# Scan.net
KiCad netlist of a schematic drawn in Altium Designer
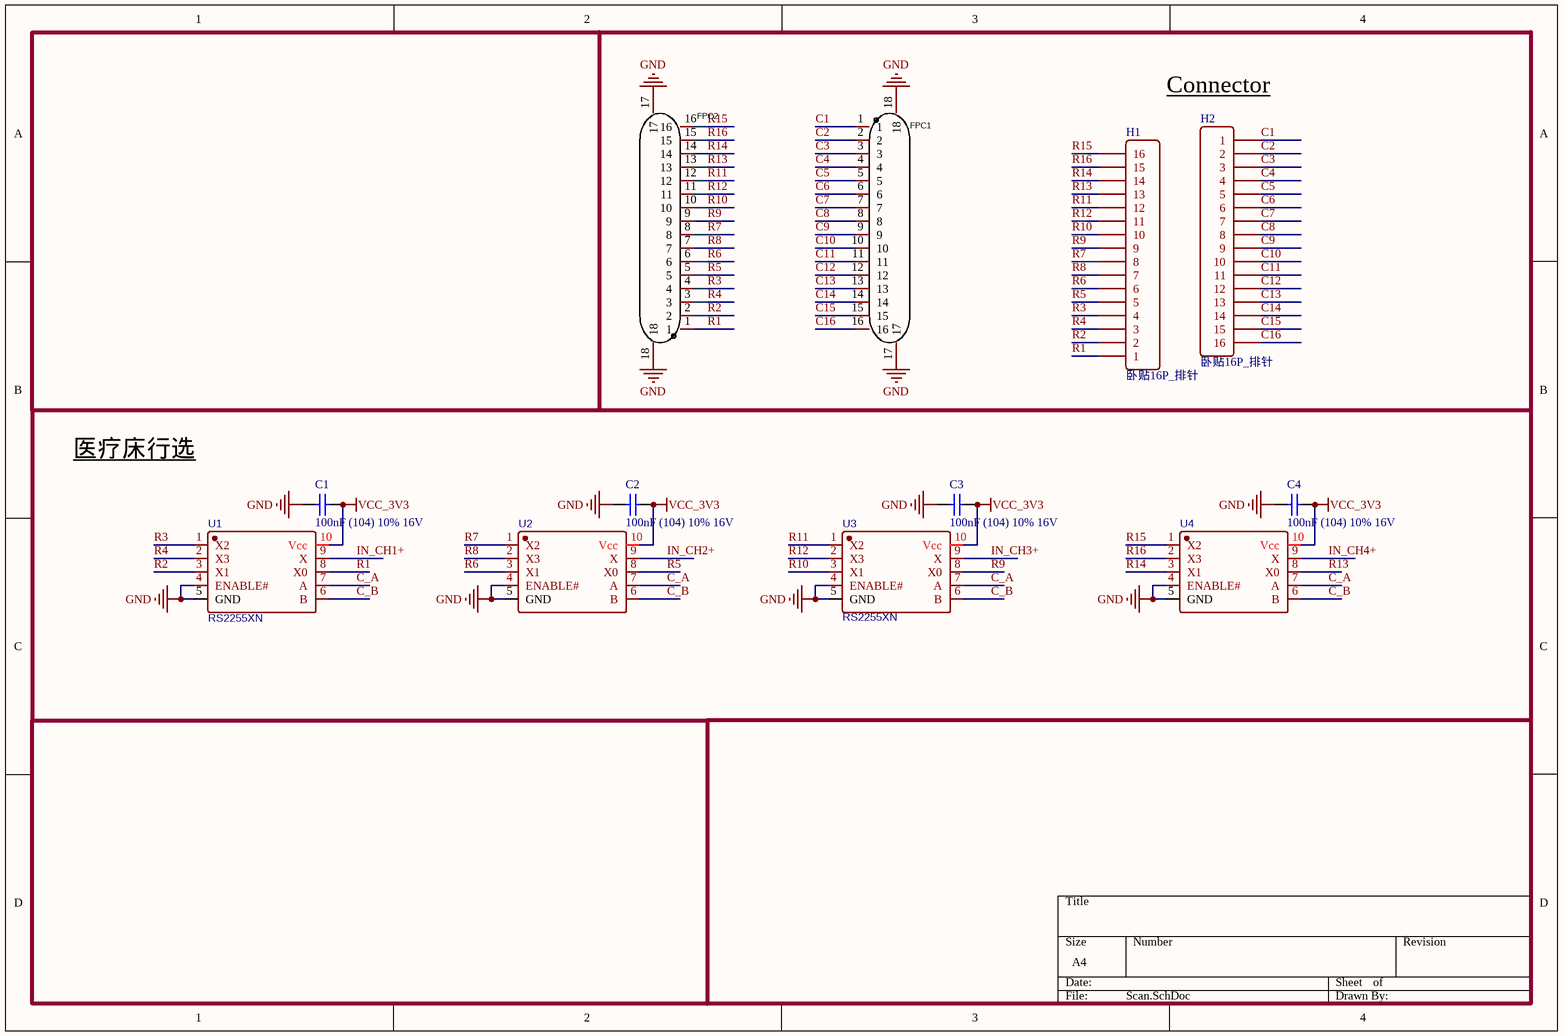
[diagram p0: Scan.SchDoc]

(export (version "E")
  (design (tool "Eeschema 10.0.6"))
  (components
    (comp (ref "C1")
      (value "100nF (104) 10% 16V")
      (footprint "0402_C")
      (description "贴片电容")
      (libsource (lib "Miscellaneous Devices LC") (part "0402 100nF (104) 10% 16V"))
    )
    (comp (ref "C2")
      (value "100nF (104) 10% 16V")
      (footprint "0402_C")
      (description "贴片电容")
      (libsource (lib "Miscellaneous Devices LC") (part "0402 100nF (104) 10% 16V"))
    )
    (comp (ref "C3")
      (value "100nF (104) 10% 16V")
      (footprint "0402_C")
      (description "贴片电容")
      (libsource (lib "Miscellaneous Devices LC") (part "0402 100nF (104) 10% 16V"))
    )
    (comp (ref "C4")
      (value "100nF (104) 10% 16V")
      (footprint "0402_C")
      (description "贴片电容")
      (libsource (lib "Miscellaneous Devices LC") (part "0402 100nF (104) 10% 16V"))
    )
    (comp (ref "FPC1")
      (value "1.0K-FX-16PWB")
      (footprint "FPC-SMD_16P-P1.00-HDGC_1.0K-FX-16PWB")
      (fields (field (name "MANUFACTURER") "HDGC(华德共创)"))
      (libsource (lib "医疗床PCB") (part "FPC_16P_抽屉式下接"))
    )
    (comp (ref "FPC2")
      (value "X10B25U16T")
      (footprint "FPC-SMD_X10B25U16T")
      (fields (field (name "MANUFACTURER") "XKB Connectivity(中国星坤)"))
      (libsource (lib "医疗床PCB") (part "FPC_16P_抽屉式上接"))
    )
    (comp (ref "H1")
      (value "卧贴16P_排针")
      (footprint "CONN-SMD_16PINS")
      (libsource (lib "医疗床PCB") (part "卧贴16P_排针"))
    )
    (comp (ref "H2")
      (value "卧贴16P_排针")
      (footprint "CONN-SMD_16PINS")
      (libsource (lib "医疗床PCB") (part "卧贴16P_排针"))
    )
    (comp (ref "U1")
      (value "RS2255XN")
      (footprint "MSOP-10_L3.0-W3.0-P0.50-LS5.0-BL")
      (fields (field (name "BOM_SUPPLIER PART") "C783421") (field (name "CONTRIBUTOR") "LCSC"))
      (libsource (lib "医疗床PCB") (part "RS2255XN"))
    )
    (comp (ref "U2")
      (value "~")
      (footprint "MSOP-10_L3.0-W3.0-P0.50-LS5.0-BL")
      (fields
        (field (name "BOM_SUPPLIER PART") "C783421")
        (field (name "BOM_MANUFACTURER PART") "RS2255XN")
        (field (name "CONTRIBUTOR") "LCSC")
      )
      (libsource (lib "医疗床PCB") (part "RS2255XN"))
    )
    (comp (ref "U3")
      (value "RS2255XN")
      (footprint "MSOP-10_L3.0-W3.0-P0.50-LS5.0-BL")
      (fields (field (name "BOM_SUPPLIER PART") "C783421") (field (name "CONTRIBUTOR") "LCSC"))
      (libsource (lib "医疗床PCB") (part "RS2255XN"))
    )
    (comp (ref "U4")
      (value "~")
      (footprint "MSOP-10_L3.0-W3.0-P0.50-LS5.0-BL")
      (fields
        (field (name "BOM_SUPPLIER PART") "C783421")
        (field (name "BOM_MANUFACTURER PART") "RS2255XN")
        (field (name "CONTRIBUTOR") "LCSC")
      )
      (libsource (lib "医疗床PCB") (part "RS2255XN"))
    )
  )
  (nets
    (net (code "1") (name "/C1") (class "Default")
      (node (ref "FPC1") (pin "1") (pinfunction "1_1") (pintype "passive"))
      (node (ref "H2") (pin "1") (pinfunction "1_1") (pintype "passive"))
    )
    (net (code "2") (name "/C2") (class "Default")
      (node (ref "FPC1") (pin "2") (pinfunction "2_2") (pintype "passive"))
      (node (ref "H2") (pin "2") (pinfunction "2_2") (pintype "passive"))
    )
    (net (code "3") (name "/C3") (class "Default")
      (node (ref "FPC1") (pin "3") (pinfunction "3_3") (pintype "passive"))
      (node (ref "H2") (pin "3") (pinfunction "3_3") (pintype "passive"))
    )
    (net (code "4") (name "/C4") (class "Default")
      (node (ref "FPC1") (pin "4") (pinfunction "4_4") (pintype "passive"))
      (node (ref "H2") (pin "4") (pinfunction "4_4") (pintype "passive"))
    )
    (net (code "5") (name "/C5") (class "Default")
      (node (ref "FPC1") (pin "5") (pinfunction "5_5") (pintype "passive"))
      (node (ref "H2") (pin "5") (pinfunction "5_5") (pintype "passive"))
    )
    (net (code "6") (name "/C6") (class "Default")
      (node (ref "FPC1") (pin "6") (pinfunction "6_6") (pintype "passive"))
      (node (ref "H2") (pin "6") (pinfunction "6_6") (pintype "passive"))
    )
    (net (code "7") (name "/C7") (class "Default")
      (node (ref "FPC1") (pin "7") (pinfunction "7_7") (pintype "passive"))
      (node (ref "H2") (pin "7") (pinfunction "7_7") (pintype "passive"))
    )
    (net (code "8") (name "/C8") (class "Default")
      (node (ref "FPC1") (pin "8") (pinfunction "8_8") (pintype "passive"))
      (node (ref "H2") (pin "8") (pinfunction "8_8") (pintype "passive"))
    )
    (net (code "9") (name "/C9") (class "Default")
      (node (ref "FPC1") (pin "9") (pinfunction "9_9") (pintype "passive"))
      (node (ref "H2") (pin "9") (pinfunction "9_9") (pintype "passive"))
    )
    (net (code "10") (name "/C10") (class "Default")
      (node (ref "FPC1") (pin "10") (pinfunction "10_10") (pintype "passive"))
      (node (ref "H2") (pin "10") (pinfunction "10_10") (pintype "passive"))
    )
    (net (code "11") (name "/C11") (class "Default")
      (node (ref "FPC1") (pin "11") (pinfunction "11_11") (pintype "passive"))
      (node (ref "H2") (pin "11") (pinfunction "11_11") (pintype "passive"))
    )
    (net (code "12") (name "/C12") (class "Default")
      (node (ref "FPC1") (pin "12") (pinfunction "12_12") (pintype "passive"))
      (node (ref "H2") (pin "12") (pinfunction "12_12") (pintype "passive"))
    )
    (net (code "13") (name "/C13") (class "Default")
      (node (ref "FPC1") (pin "13") (pinfunction "13_13") (pintype "passive"))
      (node (ref "H2") (pin "13") (pinfunction "13_13") (pintype "passive"))
    )
    (net (code "14") (name "/C14") (class "Default")
      (node (ref "FPC1") (pin "14") (pinfunction "14_14") (pintype "passive"))
      (node (ref "H2") (pin "14") (pinfunction "14_14") (pintype "passive"))
    )
    (net (code "15") (name "/C15") (class "Default")
      (node (ref "FPC1") (pin "15") (pinfunction "15_15") (pintype "passive"))
      (node (ref "H2") (pin "15") (pinfunction "15_15") (pintype "passive"))
    )
    (net (code "16") (name "/C16") (class "Default")
      (node (ref "FPC1") (pin "16") (pinfunction "16_16") (pintype "passive"))
      (node (ref "H2") (pin "16") (pinfunction "16_16") (pintype "passive"))
    )
    (net (code "17") (name "/C_A") (class "Default")
      (node (ref "U1") (pin "7") (pinfunction "A_7") (pintype "passive"))
      (node (ref "U2") (pin "7") (pinfunction "A_7") (pintype "passive"))
      (node (ref "U3") (pin "7") (pinfunction "A_7") (pintype "passive"))
      (node (ref "U4") (pin "7") (pinfunction "A_7") (pintype "passive"))
    )
    (net (code "18") (name "/C_B") (class "Default")
      (node (ref "U1") (pin "6") (pinfunction "B_6") (pintype "passive"))
      (node (ref "U2") (pin "6") (pinfunction "B_6") (pintype "passive"))
      (node (ref "U3") (pin "6") (pinfunction "B_6") (pintype "passive"))
      (node (ref "U4") (pin "6") (pinfunction "B_6") (pintype "passive"))
    )
    (net (code "19") (name "/IN_CH1+") (class "Default")
      (node (ref "U1") (pin "9") (pinfunction "X_9") (pintype "passive"))
    )
    (net (code "20") (name "/IN_CH2+") (class "Default")
      (node (ref "U2") (pin "9") (pinfunction "X_9") (pintype "passive"))
    )
    (net (code "21") (name "/IN_CH3+") (class "Default")
      (node (ref "U3") (pin "9") (pinfunction "X_9") (pintype "passive"))
    )
    (net (code "22") (name "/IN_CH4+") (class "Default")
      (node (ref "U4") (pin "9") (pinfunction "X_9") (pintype "passive"))
    )
    (net (code "23") (name "/R1") (class "Default")
      (node (ref "FPC2") (pin "1") (pinfunction "1_1") (pintype "passive"))
      (node (ref "H1") (pin "1") (pinfunction "1_1") (pintype "passive"))
      (node (ref "U1") (pin "8") (pinfunction "X0_8") (pintype "passive"))
    )
    (net (code "24") (name "/R2") (class "Default")
      (node (ref "FPC2") (pin "2") (pinfunction "2_2") (pintype "passive"))
      (node (ref "H1") (pin "2") (pinfunction "2_2") (pintype "passive"))
      (node (ref "U1") (pin "3") (pinfunction "X1_3") (pintype "passive"))
    )
    (net (code "25") (name "/R3") (class "Default")
      (node (ref "FPC2") (pin "4") (pinfunction "4_4") (pintype "passive"))
      (node (ref "H1") (pin "4") (pinfunction "4_4") (pintype "passive"))
      (node (ref "U1") (pin "1") (pinfunction "X2_1") (pintype "passive"))
    )
    (net (code "26") (name "/R4") (class "Default")
      (node (ref "FPC2") (pin "3") (pinfunction "3_3") (pintype "passive"))
      (node (ref "H1") (pin "3") (pinfunction "3_3") (pintype "passive"))
      (node (ref "U1") (pin "2") (pinfunction "X3_2") (pintype "passive"))
    )
    (net (code "27") (name "/R5") (class "Default")
      (node (ref "FPC2") (pin "5") (pinfunction "5_5") (pintype "passive"))
      (node (ref "H1") (pin "5") (pinfunction "5_5") (pintype "passive"))
      (node (ref "U2") (pin "8") (pinfunction "X0_8") (pintype "passive"))
    )
    (net (code "28") (name "/R6") (class "Default")
      (node (ref "FPC2") (pin "6") (pinfunction "6_6") (pintype "passive"))
      (node (ref "H1") (pin "6") (pinfunction "6_6") (pintype "passive"))
      (node (ref "U2") (pin "3") (pinfunction "X1_3") (pintype "passive"))
    )
    (net (code "29") (name "/R7") (class "Default")
      (node (ref "FPC2") (pin "8") (pinfunction "8_8") (pintype "passive"))
      (node (ref "H1") (pin "8") (pinfunction "8_8") (pintype "passive"))
      (node (ref "U2") (pin "1") (pinfunction "X2_1") (pintype "passive"))
    )
    (net (code "30") (name "/R8") (class "Default")
      (node (ref "FPC2") (pin "7") (pinfunction "7_7") (pintype "passive"))
      (node (ref "H1") (pin "7") (pinfunction "7_7") (pintype "passive"))
      (node (ref "U2") (pin "2") (pinfunction "X3_2") (pintype "passive"))
    )
    (net (code "31") (name "/R9") (class "Default")
      (node (ref "FPC2") (pin "9") (pinfunction "9_9") (pintype "passive"))
      (node (ref "H1") (pin "9") (pinfunction "9_9") (pintype "passive"))
      (node (ref "U3") (pin "8") (pinfunction "X0_8") (pintype "passive"))
    )
    (net (code "32") (name "/R10") (class "Default")
      (node (ref "FPC2") (pin "10") (pinfunction "10_10") (pintype "passive"))
      (node (ref "H1") (pin "10") (pinfunction "10_10") (pintype "passive"))
      (node (ref "U3") (pin "3") (pinfunction "X1_3") (pintype "passive"))
    )
    (net (code "33") (name "/R11") (class "Default")
      (node (ref "FPC2") (pin "12") (pinfunction "12_12") (pintype "passive"))
      (node (ref "H1") (pin "12") (pinfunction "12_12") (pintype "passive"))
      (node (ref "U3") (pin "1") (pinfunction "X2_1") (pintype "passive"))
    )
    (net (code "34") (name "/R12") (class "Default")
      (node (ref "FPC2") (pin "11") (pinfunction "11_11") (pintype "passive"))
      (node (ref "H1") (pin "11") (pinfunction "11_11") (pintype "passive"))
      (node (ref "U3") (pin "2") (pinfunction "X3_2") (pintype "passive"))
    )
    (net (code "35") (name "/R13") (class "Default")
      (node (ref "FPC2") (pin "13") (pinfunction "13_13") (pintype "passive"))
      (node (ref "H1") (pin "13") (pinfunction "13_13") (pintype "passive"))
      (node (ref "U4") (pin "8") (pinfunction "X0_8") (pintype "passive"))
    )
    (net (code "36") (name "/R14") (class "Default")
      (node (ref "FPC2") (pin "14") (pinfunction "14_14") (pintype "passive"))
      (node (ref "H1") (pin "14") (pinfunction "14_14") (pintype "passive"))
      (node (ref "U4") (pin "3") (pinfunction "X1_3") (pintype "passive"))
    )
    (net (code "37") (name "/R15") (class "Default")
      (node (ref "FPC2") (pin "16") (pinfunction "16_16") (pintype "passive"))
      (node (ref "H1") (pin "16") (pinfunction "16_16") (pintype "passive"))
      (node (ref "U4") (pin "1") (pinfunction "X2_1") (pintype "passive"))
    )
    (net (code "38") (name "/R16") (class "Default")
      (node (ref "FPC2") (pin "15") (pinfunction "15_15") (pintype "passive"))
      (node (ref "H1") (pin "15") (pinfunction "15_15") (pintype "passive"))
      (node (ref "U4") (pin "2") (pinfunction "X3_2") (pintype "passive"))
    )
    (net (code "39") (name "GND") (class "Default")
      (node (ref "C1") (pin "2") (pinfunction "2_2") (pintype "passive"))
      (node (ref "C2") (pin "2") (pinfunction "2_2") (pintype "passive"))
      (node (ref "C3") (pin "2") (pinfunction "2_2") (pintype "passive"))
      (node (ref "C4") (pin "2") (pinfunction "2_2") (pintype "passive"))
      (node (ref "FPC1") (pin "17") (pinfunction "17_17") (pintype "passive"))
      (node (ref "FPC1") (pin "18") (pinfunction "18_18") (pintype "passive"))
      (node (ref "FPC2") (pin "17") (pinfunction "17_17") (pintype "passive"))
      (node (ref "FPC2") (pin "18") (pinfunction "18_18") (pintype "passive"))
      (node (ref "U1") (pin "4") (pinfunction "ENABLE#_4") (pintype "passive"))
      (node (ref "U1") (pin "5") (pinfunction "GND_5") (pintype "passive"))
      (node (ref "U2") (pin "4") (pinfunction "ENABLE#_4") (pintype "passive"))
      (node (ref "U2") (pin "5") (pinfunction "GND_5") (pintype "passive"))
      (node (ref "U3") (pin "4") (pinfunction "ENABLE#_4") (pintype "passive"))
      (node (ref "U3") (pin "5") (pinfunction "GND_5") (pintype "passive"))
      (node (ref "U4") (pin "4") (pinfunction "ENABLE#_4") (pintype "passive"))
      (node (ref "U4") (pin "5") (pinfunction "GND_5") (pintype "passive"))
    )
    (net (code "40") (name "VCC_3V3") (class "Default")
      (node (ref "C1") (pin "1") (pinfunction "1_1") (pintype "passive"))
      (node (ref "C2") (pin "1") (pinfunction "1_1") (pintype "passive"))
      (node (ref "C3") (pin "1") (pinfunction "1_1") (pintype "passive"))
      (node (ref "C4") (pin "1") (pinfunction "1_1") (pintype "passive"))
      (node (ref "U1") (pin "10") (pinfunction "Vcc_10") (pintype "passive"))
      (node (ref "U2") (pin "10") (pinfunction "Vcc_10") (pintype "passive"))
      (node (ref "U3") (pin "10") (pinfunction "Vcc_10") (pintype "passive"))
      (node (ref "U4") (pin "10") (pinfunction "Vcc_10") (pintype "passive"))
    )
  )
)
